# Embedded_System_Top.net
KiCad netlist of a schematic drawn in Altium Designer
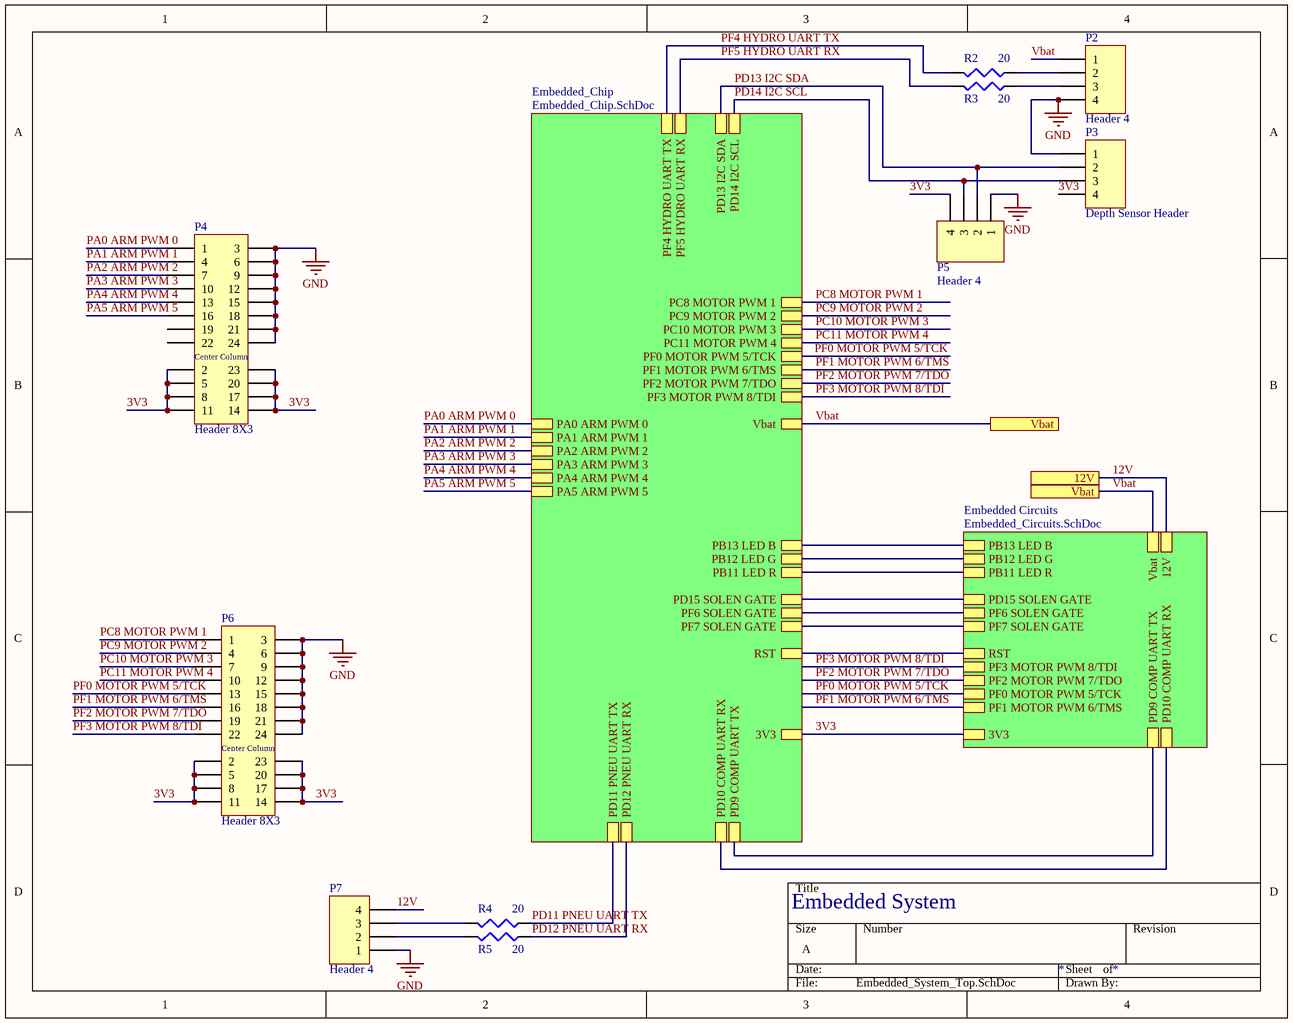
[diagram p0: Embedded_System_Top.SchDoc]

(export (version "E")
  (design (tool "Eeschema 10.0.6"))
  (components
    (comp (ref "P2")
      (value "Header 4")
      (footprint "Header 1x4")
      (description "Header, 4-Pin")
      (fields (field (name "PUBLISHER") "Altium Limited"))
      (libsource (lib "Miscellaneous Connectors") (part "Header 4"))
    )
    (comp (ref "P3")
      (value "Depth Sensor Header")
      (footprint "DF13-4P-1.25DSA")
      (description "Header, 4-Pin")
      (fields (field (name "PUBLISHER") "Altium Limited"))
      (libsource (lib "Miscellaneous Connectors") (part "Header 4"))
    )
    (comp (ref "P4")
      (value "Header 8X3")
      (footprint "Header 8X3")
      (description "Connector Header Through Hole 24 position 0.079\" (2.00mm)")
      (libsource (lib "Power_Embedded_Board_Library") (part "Header 8X3 (2mm)"))
    )
    (comp (ref "P5")
      (value "Header 4")
      (footprint "DF13-4P-1.25DSA")
      (description "Header, 4-Pin")
      (fields (field (name "PUBLISHER") "Altium Limited"))
      (libsource (lib "") (part "Header 4_1"))
    )
    (comp (ref "P6")
      (value "Header 8X3")
      (footprint "Header 8X3")
      (description "Connector Header Through Hole 24 position 0.079\" (2.00mm)")
      (libsource (lib "Power_Embedded_Board_Library") (part "Header 8X3 (2mm)"))
    )
    (comp (ref "P7")
      (value "Header 4")
      (footprint "Header 1x4")
      (description "Header, 4-Pin")
      (fields (field (name "PUBLISHER") "Altium Limited"))
      (libsource (lib "") (part "Header 4_2"))
    )
    (comp (ref "R2")
      (value "20")
      (footprint "J1-0603")
      (description "Resistor")
      (fields (field (name "Comment") "Res3") (field (name "PUBLISHER") "Altium Limited"))
      (libsource (lib "Miscellaneous Devices") (part "Res3"))
    )
    (comp (ref "R3")
      (value "20")
      (footprint "J1-0603")
      (description "Resistor")
      (fields (field (name "Comment") "Res3") (field (name "PUBLISHER") "Altium Limited"))
      (libsource (lib "Miscellaneous Devices") (part "Res3"))
    )
    (comp (ref "R4")
      (value "20")
      (footprint "J1-0603")
      (description "Resistor")
      (fields (field (name "Comment") "Res3") (field (name "PUBLISHER") "Altium Limited"))
      (libsource (lib "Miscellaneous Devices") (part "Res3"))
    )
    (comp (ref "R5")
      (value "20")
      (footprint "J1-0603")
      (description "Resistor")
      (fields (field (name "Comment") "Res3") (field (name "PUBLISHER") "Altium Limited"))
      (libsource (lib "Miscellaneous Devices") (part "Res3"))
    )
  )
  (nets
    (net (code "1") (name "/3V3") (class "Default")
      (node (ref "P3") (pin "4") (pinfunction "4_4") (pintype "passive"))
      (node (ref "P4") (pin "11") (pinfunction "11_11") (pintype "passive"))
      (node (ref "P4") (pin "14") (pinfunction "14_14") (pintype "passive"))
      (node (ref "P4") (pin "17") (pinfunction "17_17") (pintype "passive"))
      (node (ref "P4") (pin "2") (pinfunction "2_2") (pintype "passive"))
      (node (ref "P4") (pin "20") (pinfunction "20_20") (pintype "passive"))
      (node (ref "P4") (pin "23") (pinfunction "23_23") (pintype "passive"))
      (node (ref "P4") (pin "5") (pinfunction "5_5") (pintype "passive"))
      (node (ref "P4") (pin "8") (pinfunction "8_8") (pintype "passive"))
      (node (ref "P5") (pin "4") (pinfunction "4_4") (pintype "passive"))
      (node (ref "P6") (pin "11") (pinfunction "11_11") (pintype "passive"))
      (node (ref "P6") (pin "14") (pinfunction "14_14") (pintype "passive"))
      (node (ref "P6") (pin "17") (pinfunction "17_17") (pintype "passive"))
      (node (ref "P6") (pin "2") (pinfunction "2_2") (pintype "passive"))
      (node (ref "P6") (pin "20") (pinfunction "20_20") (pintype "passive"))
      (node (ref "P6") (pin "23") (pinfunction "23_23") (pintype "passive"))
      (node (ref "P6") (pin "5") (pinfunction "5_5") (pintype "passive"))
      (node (ref "P6") (pin "8") (pinfunction "8_8") (pintype "passive"))
    )
    (net (code "2") (name "/12V") (class "Default")
      (node (ref "P7") (pin "4") (pinfunction "4_4") (pintype "passive"))
    )
    (net (code "3") (name "/PA0 ARM PWM 0") (class "Default")
      (node (ref "P4") (pin "1") (pinfunction "1_1") (pintype "passive"))
    )
    (net (code "4") (name "/PA1 ARM PWM 1") (class "Default")
      (node (ref "P4") (pin "4") (pinfunction "4_4") (pintype "passive"))
    )
    (net (code "5") (name "/PA2 ARM PWM 2") (class "Default")
      (node (ref "P4") (pin "7") (pinfunction "7_7") (pintype "passive"))
    )
    (net (code "6") (name "/PA3 ARM PWM 3") (class "Default")
      (node (ref "P4") (pin "10") (pinfunction "10_10") (pintype "passive"))
    )
    (net (code "7") (name "/PA4 ARM PWM 4") (class "Default")
      (node (ref "P4") (pin "13") (pinfunction "13_13") (pintype "passive"))
    )
    (net (code "8") (name "/PA5 ARM PWM 5") (class "Default")
      (node (ref "P4") (pin "16") (pinfunction "16_16") (pintype "passive"))
    )
    (net (code "12") (name "/PC8 MOTOR PWM 1") (class "Default")
      (node (ref "P6") (pin "1") (pinfunction "1_1") (pintype "passive"))
    )
    (net (code "13") (name "/PC9 MOTOR PWM 2") (class "Default")
      (node (ref "P6") (pin "4") (pinfunction "4_4") (pintype "passive"))
    )
    (net (code "14") (name "/PC10 MOTOR PWM 3") (class "Default")
      (node (ref "P6") (pin "7") (pinfunction "7_7") (pintype "passive"))
    )
    (net (code "15") (name "/PC11 MOTOR PWM 4") (class "Default")
      (node (ref "P6") (pin "10") (pinfunction "10_10") (pintype "passive"))
    )
    (net (code "18") (name "/PD11 PNEU UART TX") (class "Default")
      (node (ref "R4") (pin "1") (pinfunction "1_1") (pintype "passive"))
    )
    (net (code "19") (name "/PD12 PNEU UART RX") (class "Default")
      (node (ref "R5") (pin "1") (pinfunction "1_1") (pintype "passive"))
    )
    (net (code "20") (name "/PD13 I2C SDA") (class "Default")
      (node (ref "P3") (pin "2") (pinfunction "2_2") (pintype "passive"))
      (node (ref "P5") (pin "2") (pinfunction "2_2") (pintype "passive"))
    )
    (net (code "21") (name "/PD14 I2C SCL") (class "Default")
      (node (ref "P3") (pin "3") (pinfunction "3_3") (pintype "passive"))
      (node (ref "P5") (pin "3") (pinfunction "3_3") (pintype "passive"))
    )
    (net (code "23") (name "/PF0 MOTOR PWM 5{slash}TCK") (class "Default")
      (node (ref "P6") (pin "13") (pinfunction "13_13") (pintype "passive"))
    )
    (net (code "24") (name "/PF1 MOTOR PWM 6{slash}TMS") (class "Default")
      (node (ref "P6") (pin "16") (pinfunction "16_16") (pintype "passive"))
    )
    (net (code "25") (name "/PF2 MOTOR PWM 7{slash}TDO") (class "Default")
      (node (ref "P6") (pin "19") (pinfunction "19_19") (pintype "passive"))
    )
    (net (code "26") (name "/PF3 MOTOR PWM 8{slash}TDI") (class "Default")
      (node (ref "P6") (pin "22") (pinfunction "22_22") (pintype "passive"))
    )
    (net (code "27") (name "/PF4 HYDRO UART TX") (class "Default")
      (node (ref "R2") (pin "2") (pinfunction "2_2") (pintype "passive"))
    )
    (net (code "28") (name "/PF5 HYDRO UART RX") (class "Default")
      (node (ref "R3") (pin "2") (pinfunction "2_2") (pintype "passive"))
    )
    (net (code "32") (name "/Vbat") (class "Default")
      (node (ref "P2") (pin "1") (pinfunction "1_1") (pintype "passive"))
    )
    (net (code "33") (name "GND") (class "Default")
      (node (ref "P2") (pin "4") (pinfunction "4_4") (pintype "passive"))
      (node (ref "P3") (pin "1") (pinfunction "1_1") (pintype "passive"))
      (node (ref "P4") (pin "12") (pinfunction "12_12") (pintype "passive"))
      (node (ref "P4") (pin "15") (pinfunction "15_15") (pintype "passive"))
      (node (ref "P4") (pin "18") (pinfunction "18_18") (pintype "passive"))
      (node (ref "P4") (pin "21") (pinfunction "21_21") (pintype "passive"))
      (node (ref "P4") (pin "24") (pinfunction "24_24") (pintype "passive"))
      (node (ref "P4") (pin "3") (pinfunction "3_3") (pintype "passive"))
      (node (ref "P4") (pin "6") (pinfunction "6_6") (pintype "passive"))
      (node (ref "P4") (pin "9") (pinfunction "9_9") (pintype "passive"))
      (node (ref "P5") (pin "1") (pinfunction "1_1") (pintype "passive"))
      (node (ref "P6") (pin "12") (pinfunction "12_12") (pintype "passive"))
      (node (ref "P6") (pin "15") (pinfunction "15_15") (pintype "passive"))
      (node (ref "P6") (pin "18") (pinfunction "18_18") (pintype "passive"))
      (node (ref "P6") (pin "21") (pinfunction "21_21") (pintype "passive"))
      (node (ref "P6") (pin "24") (pinfunction "24_24") (pintype "passive"))
      (node (ref "P6") (pin "3") (pinfunction "3_3") (pintype "passive"))
      (node (ref "P6") (pin "6") (pinfunction "6_6") (pintype "passive"))
      (node (ref "P6") (pin "9") (pinfunction "9_9") (pintype "passive"))
      (node (ref "P7") (pin "1") (pinfunction "1_1") (pintype "passive"))
    )
    (net (code "34") (name "Net-(P2-Pad2)") (class "Default")
      (node (ref "P2") (pin "2") (pinfunction "2_2") (pintype "passive"))
      (node (ref "R2") (pin "1") (pinfunction "1_1") (pintype "passive"))
    )
    (net (code "35") (name "Net-(P2-Pad3)") (class "Default")
      (node (ref "P2") (pin "3") (pinfunction "3_3") (pintype "passive"))
      (node (ref "R3") (pin "1") (pinfunction "1_1") (pintype "passive"))
    )
    (net (code "36") (name "Net-(P7-Pad2)") (class "Default")
      (node (ref "P7") (pin "2") (pinfunction "2_2") (pintype "passive"))
      (node (ref "R5") (pin "2") (pinfunction "2_2") (pintype "passive"))
    )
    (net (code "37") (name "Net-(P7-Pad3)") (class "Default")
      (node (ref "P7") (pin "3") (pinfunction "3_3") (pintype "passive"))
      (node (ref "R4") (pin "2") (pinfunction "2_2") (pintype "passive"))
    )
    (net (code "38") (name "unconnected-(P4-Pad19)") (class "Default")
      (node (ref "P4") (pin "19") (pinfunction "19_19") (pintype "passive"))
    )
    (net (code "39") (name "unconnected-(P4-Pad22)") (class "Default")
      (node (ref "P4") (pin "22") (pinfunction "22_22") (pintype "passive"))
    )
  )
)
